# v1.net
KiCad netlist of a schematic drawn in EAGLE
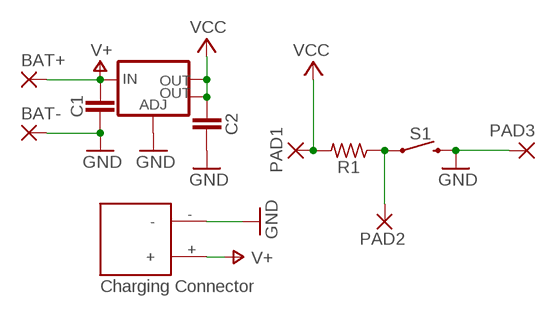
[diagram p0: schematic, sheet 1]

(export (version "E")
  (design (tool "Eeschema 10.0.6"))
  (components
    (comp (ref "BAT+")
      (value "SMD2")
      (footprint "eagle-import:SMD1,27-2,54")
      (libsource (lib "eagle-import") (part "SMD2"))
    )
    (comp (ref "BAT-")
      (value "SMD2")
      (footprint "eagle-import:SMD1,27-2,54")
      (libsource (lib "eagle-import") (part "SMD2"))
    )
    (comp (ref "C1")
      (value "C-EUC0402")
      (footprint "eagle-import:C0402")
      (libsource (lib "eagle-import") (part "C-EUC0402"))
    )
    (comp (ref "C2")
      (value "C-EUC0402")
      (footprint "eagle-import:C0402")
      (libsource (lib "eagle-import") (part "C-EUC0402"))
    )
    (comp (ref "PAD1")
      (value "SMD2")
      (footprint "eagle-import:SMD1,27-2,54")
      (libsource (lib "eagle-import") (part "SMD2"))
    )
    (comp (ref "PAD2")
      (value "SMD2")
      (footprint "eagle-import:SMD1,27-2,54")
      (libsource (lib "eagle-import") (part "SMD2"))
    )
    (comp (ref "PAD3")
      (value "SMD2")
      (footprint "eagle-import:SMD1,27-2,54")
      (libsource (lib "eagle-import") (part "SMD2"))
    )
    (comp (ref "R1")
      (value "R-US_R0402")
      (footprint "eagle-import:R0402")
      (libsource (lib "eagle-import") (part "R-US_R0402"))
    )
    (comp (ref "S1")
      (value "MOMENTARY-SWITCH-SPST-PTH-6.0MM")
      (footprint "eagle-import:TACTILE_SWITCH_PTH_6.0MM")
      (libsource (lib "eagle-import") (part "MOMENTARY-SWITCH-SPST-PTH-6.0MM"))
    )
    (comp (ref "U$1")
      (value "JST-JST-2")
      (footprint "eagle-import:JST-JST-2")
      (libsource (lib "eagle-import") (part "JST-JST-2"))
    )
    (comp (ref "U1")
      (value "V_REG_LM1117SOT223")
      (footprint "eagle-import:SOT223")
      (libsource (lib "eagle-import") (part "V_REG_LM1117SOT223"))
    )
  )
  (nets
    (net (code "1") (name "GND") (class "Default")
      (node (ref "BAT-") (pin "1") (pinfunction "P_1") (pintype "passive"))
      (node (ref "C1") (pin "1") (pinfunction "1_1") (pintype "passive"))
      (node (ref "C2") (pin "1") (pinfunction "1_1") (pintype "passive"))
      (node (ref "PAD3") (pin "1") (pinfunction "P_1") (pintype "passive"))
      (node (ref "S1") (pin "3") (pinfunction "2_3") (pintype "passive"))
      (node (ref "U$1") (pin "-") (pinfunction "-_-") (pintype "bidirectional"))
      (node (ref "U1") (pin "1") (pinfunction "ADJ_1") (pintype "input"))
    )
    (net (code "2") (name "Net-(PAD2-P)") (class "Default")
      (node (ref "PAD2") (pin "1") (pinfunction "P_1") (pintype "passive"))
      (node (ref "R1") (pin "1") (pinfunction "1_1") (pintype "passive"))
      (node (ref "S1") (pin "1") (pinfunction "1_1") (pintype "passive"))
    )
    (net (code "3") (name "V+") (class "Default")
      (node (ref "BAT+") (pin "1") (pinfunction "P_1") (pintype "passive"))
      (node (ref "C1") (pin "2") (pinfunction "2_2") (pintype "passive"))
      (node (ref "U$1") (pin "+") (pinfunction "+_+") (pintype "bidirectional"))
      (node (ref "U1") (pin "3") (pinfunction "IN_3") (pintype "input"))
    )
    (net (code "4") (name "VCC") (class "Default")
      (node (ref "C2") (pin "2") (pinfunction "2_2") (pintype "passive"))
      (node (ref "PAD1") (pin "1") (pinfunction "P_1") (pintype "passive"))
      (node (ref "R1") (pin "2") (pinfunction "2_2") (pintype "passive"))
      (node (ref "U1") (pin "2") (pinfunction "OUT_2") (pintype "output"))
      (node (ref "U1") (pin "4") (pinfunction "OUT_4") (pintype "output"))
    )
  )
)
